# baby_monitor_v1.net
KiCad netlist of a schematic drawn in EAGLE
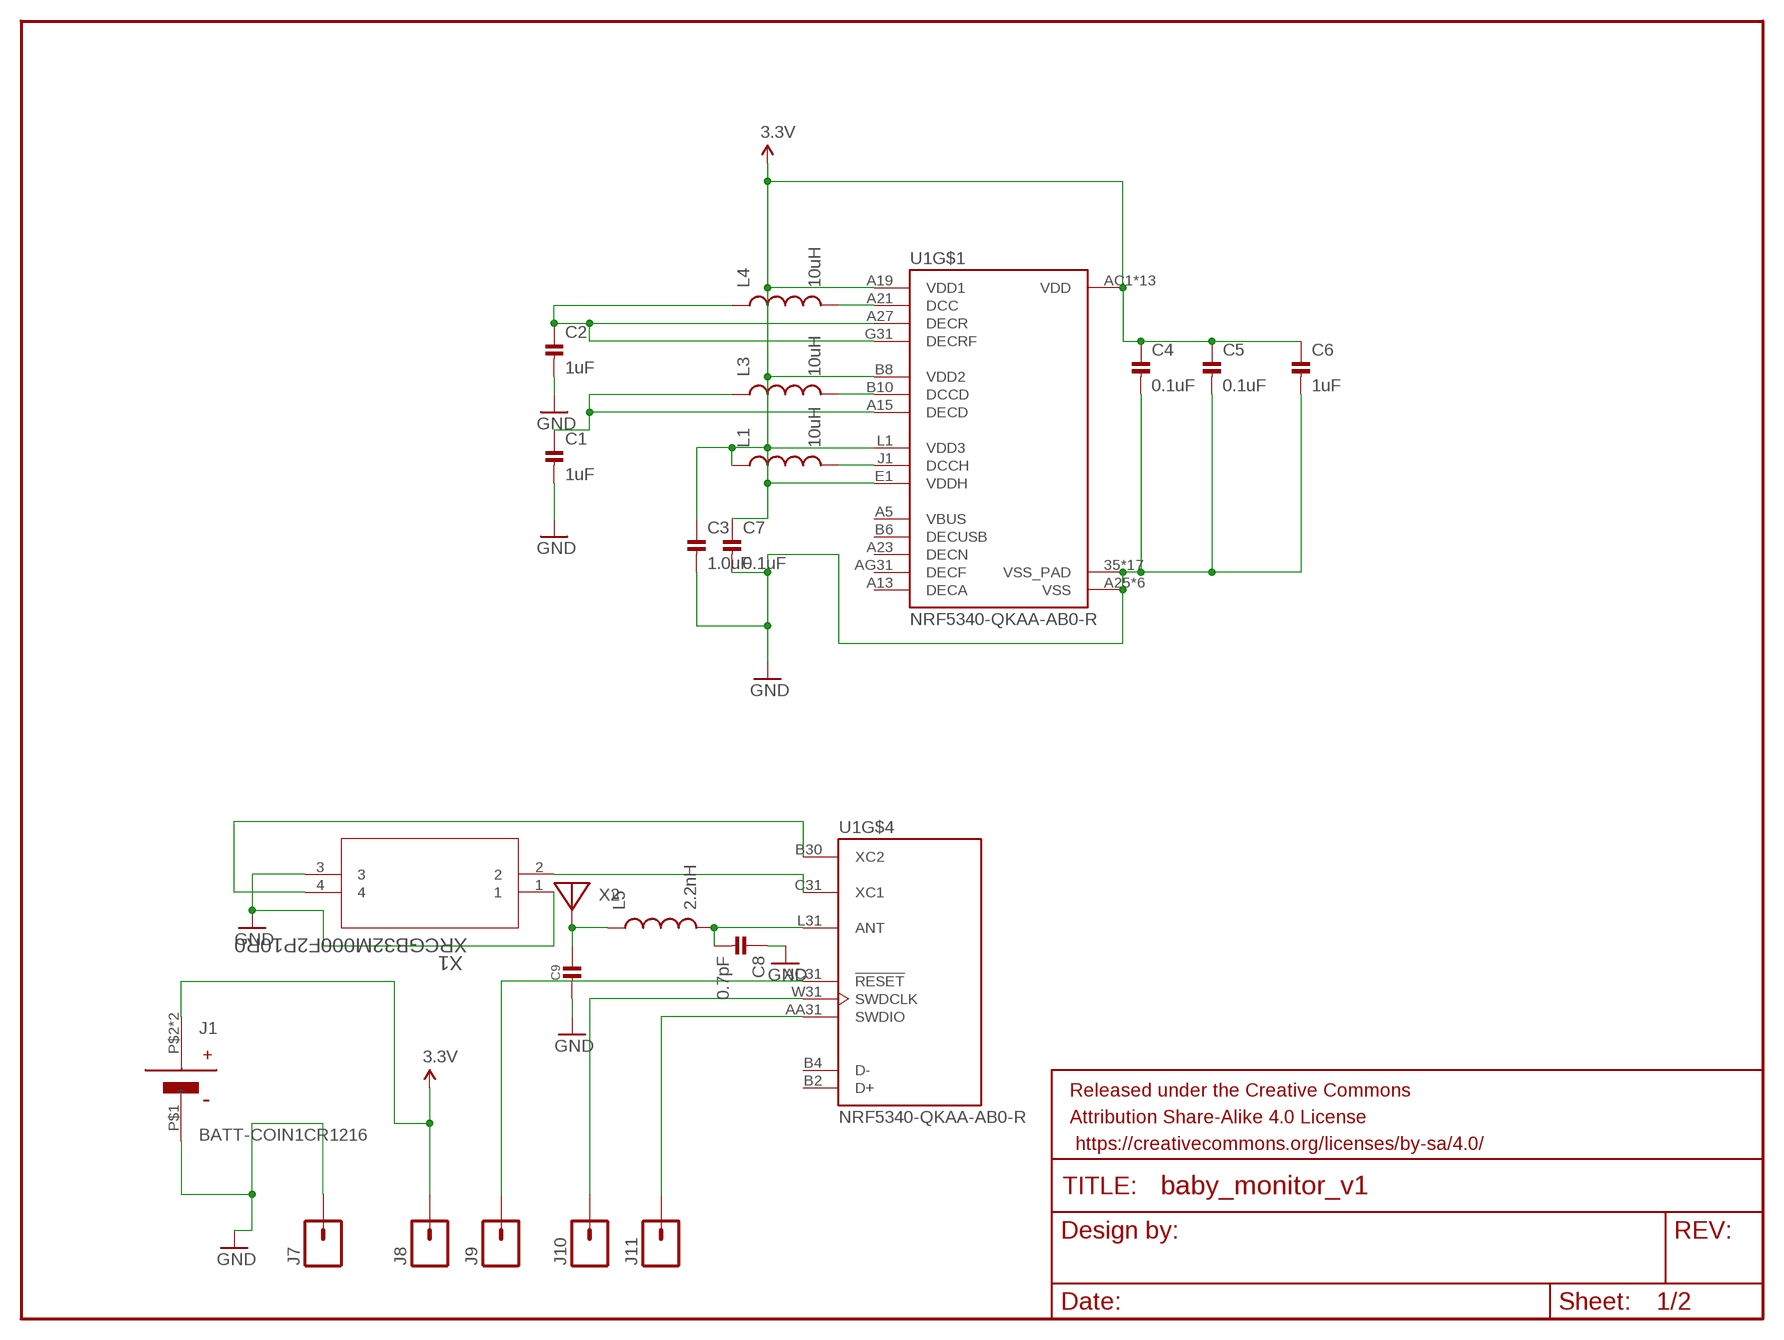
[diagram p0: schematic, sheet 1]
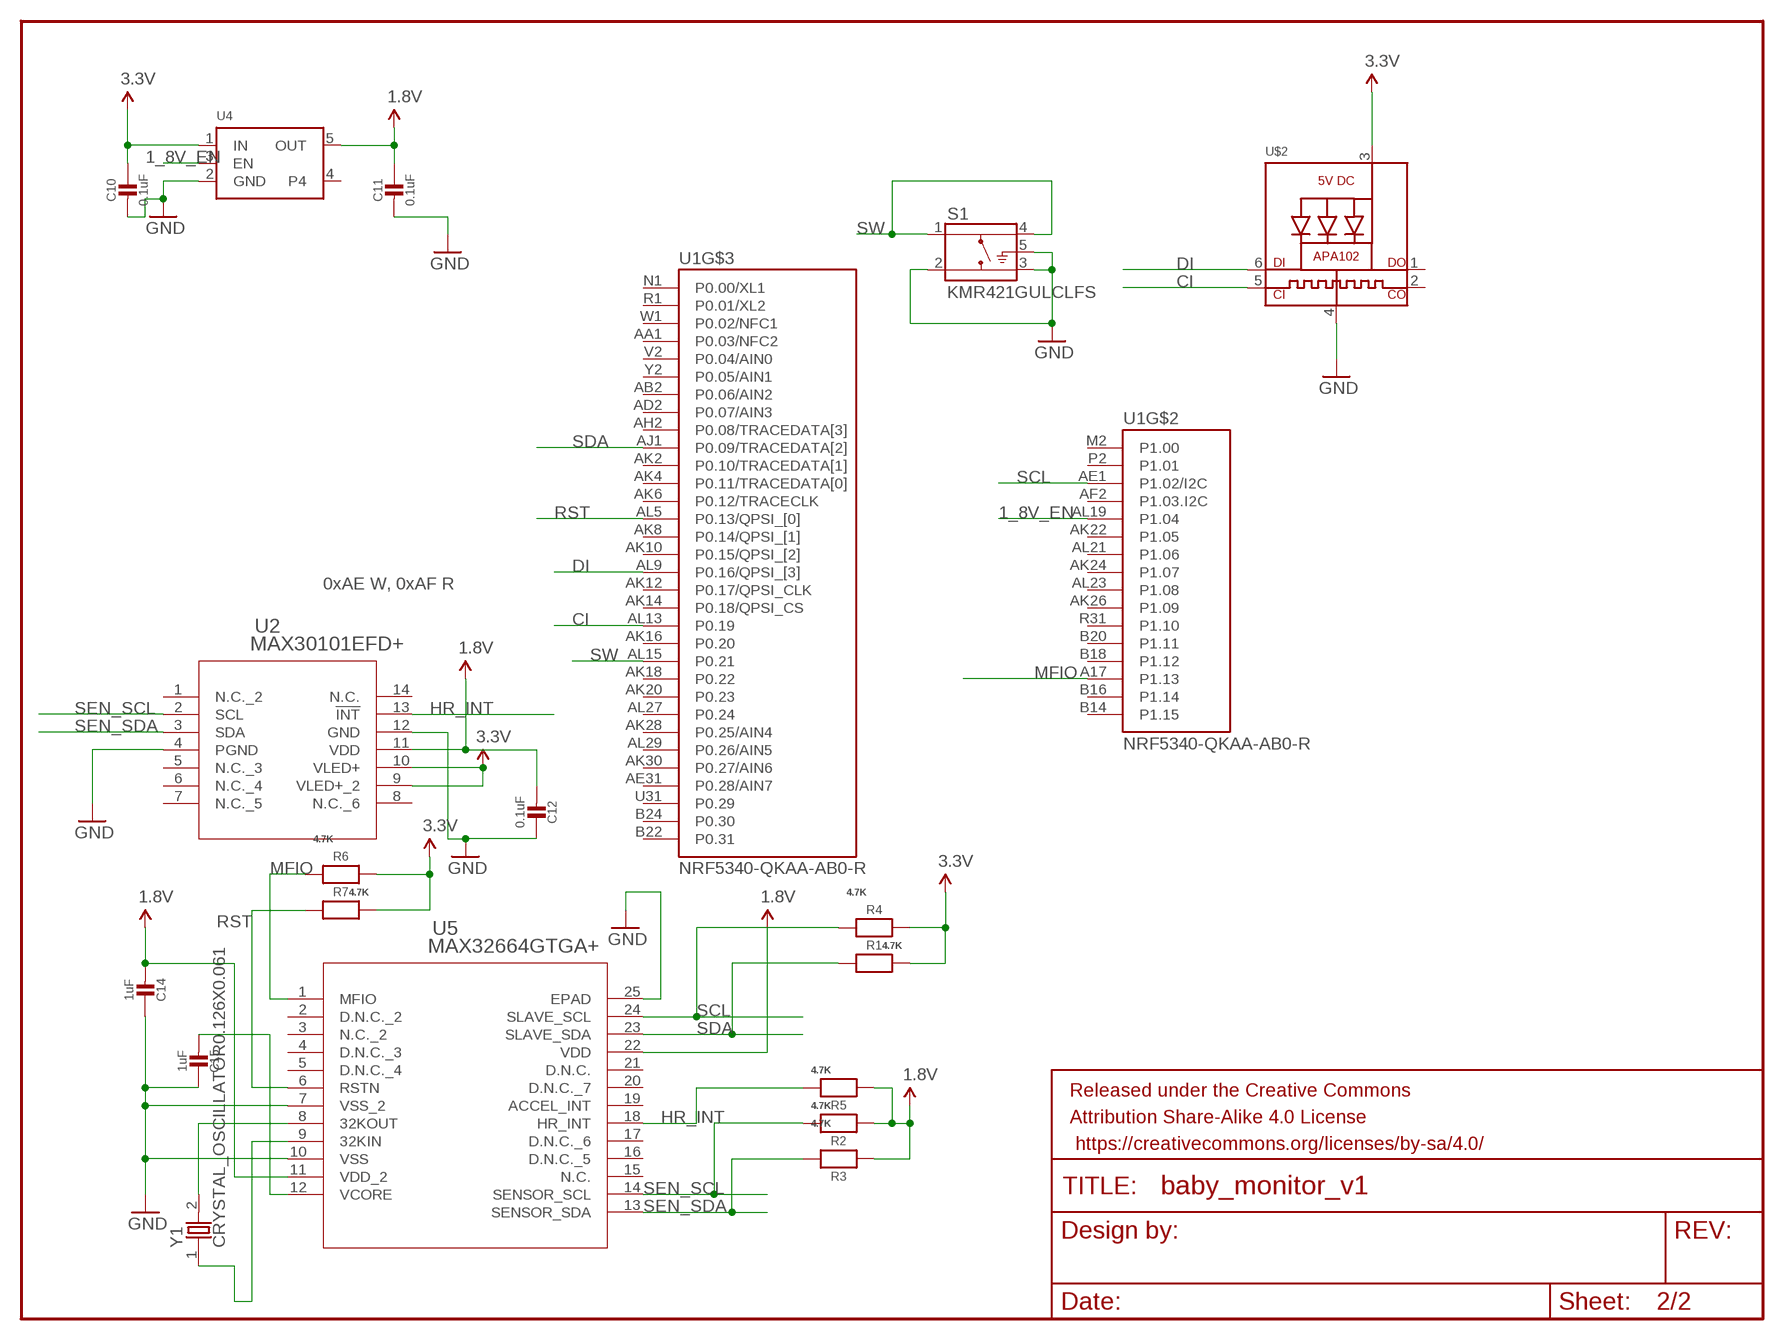
[diagram p1: schematic, sheet 2]

(export (version "E")
  (design (tool "Eeschema 10.0.6"))
  (components
    (comp (ref "C1")
      (value "1uF")
      (footprint "eagle-import:MICROBUILDER__0402MP")
      (libsource (lib "eagle-import") (part "MICROBUILDER_CAP_CERAMIC_0402MP"))
    )
    (comp (ref "C2")
      (value "1uF")
      (footprint "eagle-import:MICROBUILDER__0402MP")
      (libsource (lib "eagle-import") (part "MICROBUILDER_CAP_CERAMIC_0402MP"))
    )
    (comp (ref "C3")
      (value "1.0uF")
      (footprint "eagle-import:MICROBUILDER__0402MP")
      (libsource (lib "eagle-import") (part "MICROBUILDER_CAP_CERAMIC_0402MP"))
    )
    (comp (ref "C4")
      (value "0.1uF")
      (footprint "eagle-import:MICROBUILDER__0402MP")
      (libsource (lib "eagle-import") (part "MICROBUILDER_CAP_CERAMIC_0402MP"))
    )
    (comp (ref "C5")
      (value "0.1uF")
      (footprint "eagle-import:MICROBUILDER__0402MP")
      (libsource (lib "eagle-import") (part "MICROBUILDER_CAP_CERAMIC_0402MP"))
    )
    (comp (ref "C6")
      (value "1uF")
      (footprint "eagle-import:MICROBUILDER__0402MP")
      (libsource (lib "eagle-import") (part "MICROBUILDER_CAP_CERAMIC_0402MP"))
    )
    (comp (ref "C7")
      (value "0.1uF")
      (footprint "eagle-import:MICROBUILDER__0402MP")
      (libsource (lib "eagle-import") (part "MICROBUILDER_CAP_CERAMIC_0402MP"))
    )
    (comp (ref "C8")
      (value "0.7pF")
      (footprint "eagle-import:MICROBUILDER__0402MP")
      (libsource (lib "eagle-import") (part "MICROBUILDER_CAP_CERAMIC_0402MP"))
    )
    (comp (ref "C9")
      (value "MICROBUILDER_CAP_CERAMIC_0402MP")
      (footprint "eagle-import:MICROBUILDER__0402MP")
      (libsource (lib "eagle-import") (part "graftel-internal-ic_MICROBUILDER_CAP_CERAMIC_0402MP"))
    )
    (comp (ref "FRAME1")
      (value "FRAME-LETTERNO_PACKAGE")
      (footprint "eagle-import:DUMMY")
      (fields (field (name "DESIGNER") "Nobody"))
      (libsource (lib "eagle-import") (part "FRAME-LETTERNO_PACKAGE"))
    )
    (comp (ref "J1")
      (value "BATT-COIN1CR1216")
      (footprint "eagle-import:BC-2017-TR")
      (libsource (lib "eagle-import") (part "BATT-COIN1CR1216"))
    )
    (comp (ref "J7")
      (value "M01TINY")
      (footprint "eagle-import:1X01_TINY")
      (libsource (lib "eagle-import") (part "M01TINY"))
    )
    (comp (ref "J8")
      (value "M01TINY")
      (footprint "eagle-import:1X01_TINY")
      (libsource (lib "eagle-import") (part "M01TINY"))
    )
    (comp (ref "J9")
      (value "M01TINY")
      (footprint "eagle-import:1X01_TINY")
      (libsource (lib "eagle-import") (part "M01TINY"))
    )
    (comp (ref "J10")
      (value "M01TINY")
      (footprint "eagle-import:1X01_TINY")
      (libsource (lib "eagle-import") (part "M01TINY"))
    )
    (comp (ref "J11")
      (value "M01TINY")
      (footprint "eagle-import:1X01_TINY")
      (libsource (lib "eagle-import") (part "M01TINY"))
    )
    (comp (ref "L1")
      (value "10uH")
      (footprint "eagle-import:NORDIC_MISC_RESC0603_N")
      (libsource (lib "eagle-import") (part "NORDIC_MISC_INDUCTOR_0603_N"))
    )
    (comp (ref "L3")
      (value "10uH")
      (footprint "eagle-import:NORDIC_MISC_RESC0603_N")
      (libsource (lib "eagle-import") (part "NORDIC_MISC_INDUCTOR_0603_N"))
    )
    (comp (ref "L4")
      (value "10uH")
      (footprint "eagle-import:NORDIC_MISC_RESC0603_N")
      (libsource (lib "eagle-import") (part "NORDIC_MISC_INDUCTOR_0603_N"))
    )
    (comp (ref "L5")
      (value "2.2nH")
      (footprint "eagle-import:NORDIC_MISC_RESC0402_N")
      (libsource (lib "eagle-import") (part "NORDIC_MISC_INDUCTOR_0402_N"))
    )
    (comp (ref "U1")
      (value "NRF5340-QKAA-AB0-R")
      (footprint "eagle-import:XCVR_NRF5340-QKAA-AB0-R")
      (fields (field (name "MF") "Nordic Semiconductor") (field (name "MP") "nRF5340-QKAA-AB0-R"))
      (libsource (lib "eagle-import") (part "NRF5340-QKAA-AB0-R"))
    )
    (comp (ref "X1")
      (value "XRCGB32M000F2P10R0")
      (footprint "eagle-import:XTAL_SON4_1P6X2P0_MUR")
      (fields (field (name "DIGIKEY_PART") "490-14308-1-ND"))
      (libsource (lib "eagle-import") (part "XRCGB32M000F2P10R0"))
    )
    (comp (ref "X2")
      (value "ADAFRUIT_WIRELESS_ANTENNA_JOHANSON_2450AT18B100")
      (footprint "eagle-import:ADAFRUIT_WIRELESS_ANT_2450AT18B100")
      (fields (field (name "DIGIKEY_PART") "712-1006-1-ND"))
      (libsource (lib "eagle-import") (part "ADAFRUIT_WIRELESS_ANTENNA_JOHANSON_2450AT18B100"))
    )
    (comp (ref "C10")
      (value "0.1uF")
      (footprint "eagle-import:MICROBUILDER__0402MP")
      (libsource (lib "eagle-import") (part "MICROBUILDER_CAP_CERAMIC_0402MP"))
    )
    (comp (ref "C11")
      (value "0.1uF")
      (footprint "eagle-import:MICROBUILDER__0402MP")
      (libsource (lib "eagle-import") (part "MICROBUILDER_CAP_CERAMIC_0402MP"))
    )
    (comp (ref "C12")
      (value "0.1uF")
      (footprint "eagle-import:MICROBUILDER__0402MP")
      (libsource (lib "eagle-import") (part "MICROBUILDER_CAP_CERAMIC_0402MP"))
    )
    (comp (ref "C14")
      (value "1uF")
      (footprint "eagle-import:MICROBUILDER__0402MP")
      (libsource (lib "eagle-import") (part "MICROBUILDER_CAP_CERAMIC_0402MP"))
    )
    (comp (ref "C15")
      (value "1uF")
      (footprint "eagle-import:MICROBUILDER__0402MP")
      (libsource (lib "eagle-import") (part "MICROBUILDER_CAP_CERAMIC_0402MP"))
    )
    (comp (ref "FRAME2")
      (value "FRAME-LETTERNO_PACKAGE")
      (footprint "eagle-import:DUMMY")
      (fields (field (name "DESIGNER") "Nobody"))
      (libsource (lib "eagle-import") (part "FRAME-LETTERNO_PACKAGE"))
    )
    (comp (ref "R1")
      (value "4.7K")
      (footprint "eagle-import:MICROBUILDER__0402MP")
      (libsource (lib "eagle-import") (part "MICROBUILDER_RESISTOR_0402MP"))
    )
    (comp (ref "R2")
      (value "4.7K")
      (footprint "eagle-import:MICROBUILDER__0402MP")
      (libsource (lib "eagle-import") (part "MICROBUILDER_RESISTOR_0402MP"))
    )
    (comp (ref "R3")
      (value "4.7K")
      (footprint "eagle-import:MICROBUILDER__0402MP")
      (libsource (lib "eagle-import") (part "MICROBUILDER_RESISTOR_0402MP"))
    )
    (comp (ref "R4")
      (value "4.7K")
      (footprint "eagle-import:MICROBUILDER__0402MP")
      (libsource (lib "eagle-import") (part "MICROBUILDER_RESISTOR_0402MP"))
    )
    (comp (ref "R5")
      (value "4.7K")
      (footprint "eagle-import:MICROBUILDER__0402MP")
      (libsource (lib "eagle-import") (part "MICROBUILDER_RESISTOR_0402MP"))
    )
    (comp (ref "R6")
      (value "4.7K")
      (footprint "eagle-import:MICROBUILDER__0402MP")
      (libsource (lib "eagle-import") (part "MICROBUILDER_RESISTOR_0402MP"))
    )
    (comp (ref "R7")
      (value "4.7K")
      (footprint "eagle-import:MICROBUILDER__0402MP")
      (libsource (lib "eagle-import") (part "MICROBUILDER_RESISTOR_0402MP"))
    )
    (comp (ref "S1")
      (value "KMR421GULCLFS")
      (footprint "eagle-import:SW_KMR421GULCLFS")
      (fields (field (name "DIGI-KEY_PART_NUMBER") "CKN12152CT-ND") (field (name "MF") "C&K"))
      (libsource (lib "eagle-import") (part "KMR421GULCLFS"))
    )
    (comp (ref "U$2")
      (value "MICROBUILDER_APA1022020")
      (footprint "eagle-import:MICROBUILDER_APA102_2020")
      (libsource (lib "eagle-import") (part "MICROBUILDER_APA1022020"))
    )
    (comp (ref "U2")
      (value "MAX30101EFD+")
      (footprint "eagle-import:21-0880B_MXM")
      (libsource (lib "eagle-import") (part "MAX30101EFD+"))
    )
    (comp (ref "U4")
      (value "MICROBUILDER_VREG_SOT23-5")
      (footprint "eagle-import:MICROBUILDER_SOT23-5")
      (libsource (lib "eagle-import") (part "MICROBUILDER_VREG_SOT23-5"))
    )
    (comp (ref "U5")
      (value "MAX32664GTGA+")
      (footprint "eagle-import:21-100264_90-100089_MXM")
      (fields (field (name "COPYRIGHT") "Copyright (C) 2018 Accelerated Designs. All rights reserved"))
      (libsource (lib "eagle-import") (part "MAX32664GTGA+"))
    )
    (comp (ref "Y1")
      (value "CRYSTAL_OSCILLATOR0.126X0.061")
      (footprint "eagle-import:QUARTZ")
      (fields (field (name "PARTNO") "SER4072CT-ND "))
      (libsource (lib "eagle-import") (part "CRYSTAL_OSCILLATOR0.126X0.061"))
    )
  )
  (nets
    (net (code "1") (name "1.8V") (class "Default")
      (node (ref "C11") (pin "1") (pinfunction "1_1") (pintype "passive"))
      (node (ref "C12") (pin "2") (pinfunction "2_2") (pintype "passive"))
      (node (ref "C14") (pin "2") (pinfunction "2_2") (pintype "passive"))
      (node (ref "R2") (pin "1") (pinfunction "1_1") (pintype "passive"))
      (node (ref "R3") (pin "1") (pinfunction "1_1") (pintype "passive"))
      (node (ref "R5") (pin "1") (pinfunction "1_1") (pintype "passive"))
      (node (ref "U2") (pin "11") (pinfunction "VDD_11") (pintype "power_in"))
      (node (ref "U4") (pin "5") (pinfunction "OUT_5") (pintype "power_in"))
      (node (ref "U5") (pin "11") (pinfunction "VDD_2_11") (pintype "power_in"))
      (node (ref "U5") (pin "22") (pinfunction "VDD_22") (pintype "power_in"))
    )
    (net (code "2") (name "1_8V_EN") (class "Default")
      (node (ref "U1") (pin "AL19") (pinfunction "P1.04_AL19") (pintype "bidirectional"))
      (node (ref "U4") (pin "3") (pinfunction "EN_3") (pintype "input"))
    )
    (net (code "3") (name "3.3V") (class "Default")
      (node (ref "C10") (pin "1") (pinfunction "1_1") (pintype "passive"))
      (node (ref "C3") (pin "1") (pinfunction "1_1") (pintype "passive"))
      (node (ref "C4") (pin "1") (pinfunction "1_1") (pintype "passive"))
      (node (ref "C5") (pin "1") (pinfunction "1_1") (pintype "passive"))
      (node (ref "C6") (pin "1") (pinfunction "1_1") (pintype "passive"))
      (node (ref "C7") (pin "1") (pinfunction "1_1") (pintype "passive"))
      (node (ref "J1") (pin "P$2") (pinfunction "+_P$2") (pintype "bidirectional"))
      (node (ref "J1") (pin "P$3") (pinfunction "+_P$3") (pintype "bidirectional"))
      (node (ref "J8") (pin "P$1") (pinfunction "1_P$1") (pintype "passive"))
      (node (ref "L1") (pin "1") (pinfunction "1_1") (pintype "passive"))
      (node (ref "R1") (pin "2") (pinfunction "2_2") (pintype "passive"))
      (node (ref "R4") (pin "2") (pinfunction "2_2") (pintype "passive"))
      (node (ref "R6") (pin "2") (pinfunction "2_2") (pintype "passive"))
      (node (ref "R7") (pin "2") (pinfunction "2_2") (pintype "passive"))
      (node (ref "U$2") (pin "3") (pinfunction "VDD_3") (pintype "power_in"))
      (node (ref "U1") (pin "A19") (pinfunction "VDD1_A19") (pintype "power_in"))
      (node (ref "U1") (pin "AC1") (pinfunction "VDD_AC1") (pintype "power_in"))
      (node (ref "U1") (pin "AG1") (pinfunction "VDD_AG1") (pintype "power_in"))
      (node (ref "U1") (pin "AJ31") (pinfunction "VDD_AJ31") (pintype "power_in"))
      (node (ref "U1") (pin "AL11") (pinfunction "VDD_AL11") (pintype "power_in"))
      (node (ref "U1") (pin "AL17") (pinfunction "VDD_AL17") (pintype "power_in"))
      (node (ref "U1") (pin "AL25") (pinfunction "VDD_AL25") (pintype "power_in"))
      (node (ref "U1") (pin "AL3") (pinfunction "VDD_AL3") (pintype "power_in"))
      (node (ref "U1") (pin "AL7") (pinfunction "VDD_AL7") (pintype "power_in"))
      (node (ref "U1") (pin "B28") (pinfunction "VDD_B28") (pintype "power_in"))
      (node (ref "U1") (pin "B8") (pinfunction "VDD2_B8") (pintype "power_in"))
      (node (ref "U1") (pin "C1") (pinfunction "VDD_C1") (pintype "power_in"))
      (node (ref "U1") (pin "E1") (pinfunction "VDDH_E1") (pintype "power_in"))
      (node (ref "U1") (pin "E31") (pinfunction "VDD_E31") (pintype "power_in"))
      (node (ref "U1") (pin "L1") (pinfunction "VDD3_L1") (pintype "power_in"))
      (node (ref "U1") (pin "N31") (pinfunction "VDD_N31") (pintype "power_in"))
      (node (ref "U1") (pin "U1") (pinfunction "VDD_U1") (pintype "power_in"))
      (node (ref "U2") (pin "10") (pinfunction "VLED+_10") (pintype "passive"))
      (node (ref "U2") (pin "9") (pinfunction "VLED+_2_9") (pintype "passive"))
      (node (ref "U4") (pin "1") (pinfunction "IN_1") (pintype "power_in"))
    )
    (net (code "4") (name "CI") (class "Default")
      (node (ref "U$2") (pin "5") (pinfunction "CKI_5") (pintype "input"))
      (node (ref "U1") (pin "AL13") (pinfunction "P0.19_AL13") (pintype "bidirectional"))
    )
    (net (code "5") (name "DECA") (class "Default")
      (node (ref "U1") (pin "A13") (pinfunction "DECA_A13") (pintype "power_in"))
    )
    (net (code "6") (name "DECF") (class "Default")
      (node (ref "U1") (pin "AG31") (pinfunction "DECF_AG31") (pintype "power_in"))
    )
    (net (code "7") (name "DECN") (class "Default")
      (node (ref "U1") (pin "A23") (pinfunction "DECN_A23") (pintype "power_in"))
    )
    (net (code "8") (name "DECUSB") (class "Default")
      (node (ref "U1") (pin "B6") (pinfunction "DECUSB_B6") (pintype "power_in"))
    )
    (net (code "9") (name "DI") (class "Default")
      (node (ref "U$2") (pin "6") (pinfunction "DI_6") (pintype "input"))
      (node (ref "U1") (pin "AL9") (pinfunction "P0.16/QPSI_[3]_AL9") (pintype "bidirectional"))
    )
    (net (code "10") (name "GND") (class "Default")
      (node (ref "C1") (pin "2") (pinfunction "2_2") (pintype "passive"))
      (node (ref "C10") (pin "2") (pinfunction "2_2") (pintype "passive"))
      (node (ref "C11") (pin "2") (pinfunction "2_2") (pintype "passive"))
      (node (ref "C12") (pin "1") (pinfunction "1_1") (pintype "passive"))
      (node (ref "C14") (pin "1") (pinfunction "1_1") (pintype "passive"))
      (node (ref "C15") (pin "1") (pinfunction "1_1") (pintype "passive"))
      (node (ref "C2") (pin "2") (pinfunction "2_2") (pintype "passive"))
      (node (ref "C3") (pin "2") (pinfunction "2_2") (pintype "passive"))
      (node (ref "C4") (pin "2") (pinfunction "2_2") (pintype "passive"))
      (node (ref "C5") (pin "2") (pinfunction "2_2") (pintype "passive"))
      (node (ref "C6") (pin "2") (pinfunction "2_2") (pintype "passive"))
      (node (ref "C7") (pin "2") (pinfunction "2_2") (pintype "passive"))
      (node (ref "C8") (pin "1") (pinfunction "1_1") (pintype "passive"))
      (node (ref "C9") (pin "2") (pinfunction "2_2") (pintype "passive"))
      (node (ref "J1") (pin "P$1") (pinfunction "-_P$1") (pintype "bidirectional"))
      (node (ref "J7") (pin "P$1") (pinfunction "1_P$1") (pintype "passive"))
      (node (ref "S1") (pin "2") (pinfunction "2_2") (pintype "passive"))
      (node (ref "S1") (pin "3") (pinfunction "3_3") (pintype "passive"))
      (node (ref "S1") (pin "5") (pinfunction "G_5") (pintype "power_in"))
      (node (ref "U$2") (pin "4") (pinfunction "GND_4") (pintype "power_in"))
      (node (ref "U1") (pin "104") (pinfunction "VSS_PAD_104") (pintype "power_in"))
      (node (ref "U1") (pin "35") (pinfunction "VSS_PAD_35") (pintype "power_in"))
      (node (ref "U1") (pin "36") (pinfunction "VSS_PAD_36") (pintype "power_in"))
      (node (ref "U1") (pin "37") (pinfunction "VSS_PAD_37") (pintype "power_in"))
      (node (ref "U1") (pin "38") (pinfunction "VSS_PAD_38") (pintype "power_in"))
      (node (ref "U1") (pin "39") (pinfunction "VSS_PAD_39") (pintype "power_in"))
      (node (ref "U1") (pin "40") (pinfunction "VSS_PAD_40") (pintype "power_in"))
      (node (ref "U1") (pin "41") (pinfunction "VSS_PAD_41") (pintype "power_in"))
      (node (ref "U1") (pin "43") (pinfunction "VSS_PAD_43") (pintype "power_in"))
      (node (ref "U1") (pin "44") (pinfunction "VSS_PAD_44") (pintype "power_in"))
      (node (ref "U1") (pin "45") (pinfunction "VSS_PAD_45") (pintype "power_in"))
      (node (ref "U1") (pin "46") (pinfunction "VSS_PAD_46") (pintype "power_in"))
      (node (ref "U1") (pin "47") (pinfunction "VSS_PAD_47") (pintype "power_in"))
      (node (ref "U1") (pin "48") (pinfunction "VSS_PAD_48") (pintype "power_in"))
      (node (ref "U1") (pin "49") (pinfunction "VSS_PAD_49") (pintype "power_in"))
      (node (ref "U1") (pin "50") (pinfunction "VSS_PAD_50") (pintype "power_in"))
      (node (ref "U1") (pin "51") (pinfunction "VSS_PAD_51") (pintype "power_in"))
      (node (ref "U1") (pin "A25") (pinfunction "VSS_A25") (pintype "power_in"))
      (node (ref "U1") (pin "B12") (pinfunction "VSS_B12") (pintype "power_in"))
      (node (ref "U1") (pin "B26") (pinfunction "VSS_B26") (pintype "power_in"))
      (node (ref "U1") (pin "G1") (pinfunction "VSS_G1") (pintype "power_in"))
      (node (ref "U1") (pin "H2") (pinfunction "VSS_H2") (pintype "power_in"))
      (node (ref "U1") (pin "J31") (pinfunction "VSS_J31") (pintype "power_in"))
      (node (ref "U2") (pin "12") (pinfunction "GND_12") (pintype "passive"))
      (node (ref "U2") (pin "4") (pinfunction "PGND_4") (pintype "passive"))
      (node (ref "U4") (pin "2") (pinfunction "GND_2") (pintype "power_in"))
      (node (ref "U5") (pin "10") (pinfunction "VSS_10") (pintype "power_in"))
      (node (ref "U5") (pin "25") (pinfunction "EPAD_25") (pintype "power_in"))
      (node (ref "U5") (pin "7") (pinfunction "VSS_2_7") (pintype "power_in"))
      (node (ref "X1") (pin "1") (pinfunction "1_1") (pintype "passive"))
      (node (ref "X1") (pin "3") (pinfunction "3_3") (pintype "passive"))
    )
    (net (code "11") (name "HR_INT") (class "Default")
      (node (ref "R5") (pin "2") (pinfunction "2_2") (pintype "passive"))
      (node (ref "U2") (pin "13") (pinfunction "~{INT}_13") (pintype "passive"))
      (node (ref "U5") (pin "18") (pinfunction "HR_INT_18") (pintype "input"))
    )
    (net (code "12") (name "MFIO") (class "Default")
      (node (ref "R6") (pin "1") (pinfunction "1_1") (pintype "passive"))
      (node (ref "U1") (pin "A17") (pinfunction "P1.13_A17") (pintype "bidirectional"))
      (node (ref "U5") (pin "1") (pinfunction "MFIO_1") (pintype "bidirectional"))
    )
    (net (code "13") (name "Net-(J9-1)") (class "Default")
      (node (ref "J9") (pin "P$1") (pinfunction "1_P$1") (pintype "passive"))
      (node (ref "U1") (pin "AC31") (pinfunction "~{RESET}_AC31") (pintype "input"))
    )
    (net (code "14") (name "Net-(J10-1)") (class "Default")
      (node (ref "J10") (pin "P$1") (pinfunction "1_P$1") (pintype "passive"))
      (node (ref "U1") (pin "W31") (pinfunction "SWDCLK_W31") (pintype "input"))
    )
    (net (code "15") (name "Net-(J11-1)") (class "Default")
      (node (ref "J11") (pin "P$1") (pinfunction "1_P$1") (pintype "passive"))
      (node (ref "U1") (pin "AA31") (pinfunction "SWDIO_AA31") (pintype "bidirectional"))
    )
    (net (code "16") (name "Net-(U1A-DCC)") (class "Default")
      (node (ref "L4") (pin "2") (pinfunction "2_2") (pintype "passive"))
      (node (ref "U1") (pin "A21") (pinfunction "DCC_A21") (pintype "output"))
    )
    (net (code "17") (name "Net-(U1A-DCCD)") (class "Default")
      (node (ref "L3") (pin "2") (pinfunction "2_2") (pintype "passive"))
      (node (ref "U1") (pin "B10") (pinfunction "DCCD_B10") (pintype "power_in"))
    )
    (net (code "18") (name "Net-(U1A-DCCH)") (class "Default")
      (node (ref "L1") (pin "2") (pinfunction "2_2") (pintype "passive"))
      (node (ref "U1") (pin "J1") (pinfunction "DCCH_J1") (pintype "power_in"))
    )
    (net (code "19") (name "Net-(U1A-DECD)") (class "Default")
      (node (ref "C1") (pin "1") (pinfunction "1_1") (pintype "passive"))
      (node (ref "L3") (pin "1") (pinfunction "1_1") (pintype "passive"))
      (node (ref "U1") (pin "A15") (pinfunction "DECD_A15") (pintype "power_in"))
    )
    (net (code "20") (name "Net-(U1A-DECR)") (class "Default")
      (node (ref "C2") (pin "1") (pinfunction "1_1") (pintype "passive"))
      (node (ref "L4") (pin "1") (pinfunction "1_1") (pintype "passive"))
      (node (ref "U1") (pin "A27") (pinfunction "DECR_A27") (pintype "power_in"))
      (node (ref "U1") (pin "G31") (pinfunction "DECRF_G31") (pintype "power_in"))
    )
    (net (code "21") (name "Net-(U1D-ANT)") (class "Default")
      (node (ref "C8") (pin "2") (pinfunction "2_2") (pintype "passive"))
      (node (ref "L5") (pin "2") (pinfunction "2_2") (pintype "passive"))
      (node (ref "U1") (pin "L31") (pinfunction "ANT_L31") (pintype "bidirectional"))
    )
    (net (code "22") (name "Net-(U1D-XC1)") (class "Default")
      (node (ref "U1") (pin "C31") (pinfunction "XC1_C31") (pintype "input"))
      (node (ref "X1") (pin "2") (pinfunction "2_2") (pintype "passive"))
    )
    (net (code "23") (name "Net-(U1D-XC2)") (class "Default")
      (node (ref "U1") (pin "B30") (pinfunction "XC2_B30") (pintype "output"))
      (node (ref "X1") (pin "4") (pinfunction "4_4") (pintype "passive"))
    )
    (net (code "24") (name "Net-(U5-32KIN)") (class "Default")
      (node (ref "U5") (pin "9") (pinfunction "32KIN_9") (pintype "input"))
      (node (ref "Y1") (pin "1") (pinfunction "1_1") (pintype "passive"))
    )
    (net (code "25") (name "Net-(U5-32KOUT)") (class "Default")
      (node (ref "U5") (pin "8") (pinfunction "32KOUT_8") (pintype "output"))
      (node (ref "Y1") (pin "2") (pinfunction "2_2") (pintype "passive"))
    )
    (net (code "26") (name "Net-(U5-VCORE)") (class "Default")
      (node (ref "C15") (pin "2") (pinfunction "2_2") (pintype "passive"))
      (node (ref "U5") (pin "12") (pinfunction "VCORE_12") (pintype "power_in"))
    )
    (net (code "27") (name "Net-(X2-P$1)") (class "Default")
      (node (ref "C9") (pin "1") (pinfunction "1_1") (pintype "passive"))
      (node (ref "L5") (pin "1") (pinfunction "1_1") (pintype "passive"))
      (node (ref "X2") (pin "FP") (pinfunction "P$1_FP") (pintype "passive"))
    )
    (net (code "28") (name "RST") (class "Default")
      (node (ref "R7") (pin "1") (pinfunction "1_1") (pintype "passive"))
      (node (ref "U1") (pin "AL5") (pinfunction "P0.13/QPSI_[0]_AL5") (pintype "bidirectional"))
      (node (ref "U5") (pin "6") (pinfunction "RSTN_6") (pintype "input"))
    )
    (net (code "29") (name "SCL") (class "Default")
      (node (ref "R4") (pin "1") (pinfunction "1_1") (pintype "passive"))
      (node (ref "U1") (pin "AE1") (pinfunction "P1.02/I2C_AE1") (pintype "bidirectional"))
      (node (ref "U5") (pin "24") (pinfunction "SLAVE_SCL_24") (pintype "passive"))
    )
    (net (code "30") (name "SDA") (class "Default")
      (node (ref "R1") (pin "1") (pinfunction "1_1") (pintype "passive"))
      (node (ref "U1") (pin "AJ1") (pinfunction "P0.09/TRACEDATA[2]_AJ1") (pintype "bidirectional"))
      (node (ref "U5") (pin "23") (pinfunction "SLAVE_SDA_23") (pintype "passive"))
    )
    (net (code "31") (name "SEN_SCL") (class "Default")
      (node (ref "R2") (pin "2") (pinfunction "2_2") (pintype "passive"))
      (node (ref "U2") (pin "2") (pinfunction "SCL_2") (pintype "passive"))
      (node (ref "U5") (pin "14") (pinfunction "SENSOR_SCL_14") (pintype "passive"))
    )
    (net (code "32") (name "SEN_SDA") (class "Default")
      (node (ref "R3") (pin "2") (pinfunction "2_2") (pintype "passive"))
      (node (ref "U2") (pin "3") (pinfunction "SDA_3") (pintype "passive"))
      (node (ref "U5") (pin "13") (pinfunction "SENSOR_SDA_13") (pintype "passive"))
    )
    (net (code "33") (name "SW") (class "Default")
      (node (ref "S1") (pin "1") (pinfunction "1_1") (pintype "passive"))
      (node (ref "S1") (pin "4") (pinfunction "4_4") (pintype "passive"))
      (node (ref "U1") (pin "AL15") (pinfunction "P0.21_AL15") (pintype "bidirectional"))
    )
    (net (code "34") (name "VBUS") (class "Default")
      (node (ref "U1") (pin "A5") (pinfunction "VBUS_A5") (pintype "power_in"))
    )
    (net (code "35") (name "unconnected-(U$2-CKO-Pad2)") (class "Default")
      (node (ref "U$2") (pin "2") (pinfunction "CKO_2") (pintype "output"))
    )
    (net (code "36") (name "unconnected-(U$2-DO-Pad1)") (class "Default")
      (node (ref "U$2") (pin "1") (pinfunction "DO_1") (pintype "output"))
    )
    (net (code "37") (name "unconnected-(U1B-P1.00-PadM2)") (class "Default")
      (node (ref "U1") (pin "M2") (pinfunction "P1.00_M2") (pintype "bidirectional"))
    )
    (net (code "38") (name "unconnected-(U1B-P1.01-PadP2)") (class "Default")
      (node (ref "U1") (pin "P2") (pinfunction "P1.01_P2") (pintype "bidirectional"))
    )
    (net (code "39") (name "unconnected-(U1B-P1.03.I2C-PadAF2)") (class "Default")
      (node (ref "U1") (pin "AF2") (pinfunction "P1.03.I2C_AF2") (pintype "bidirectional"))
    )
    (net (code "40") (name "unconnected-(U1B-P1.05-PadAK22)") (class "Default")
      (node (ref "U1") (pin "AK22") (pinfunction "P1.05_AK22") (pintype "bidirectional"))
    )
    (net (code "41") (name "unconnected-(U1B-P1.06-PadAL21)") (class "Default")
      (node (ref "U1") (pin "AL21") (pinfunction "P1.06_AL21") (pintype "bidirectional"))
    )
    (net (code "42") (name "unconnected-(U1B-P1.07-PadAK24)") (class "Default")
      (node (ref "U1") (pin "AK24") (pinfunction "P1.07_AK24") (pintype "bidirectional"))
    )
    (net (code "43") (name "unconnected-(U1B-P1.08-PadAL23)") (class "Default")
      (node (ref "U1") (pin "AL23") (pinfunction "P1.08_AL23") (pintype "bidirectional"))
    )
    (net (code "44") (name "unconnected-(U1B-P1.09-PadAK26)") (class "Default")
      (node (ref "U1") (pin "AK26") (pinfunction "P1.09_AK26") (pintype "bidirectional"))
    )
    (net (code "45") (name "unconnected-(U1B-P1.10-PadR31)") (class "Default")
      (node (ref "U1") (pin "R31") (pinfunction "P1.10_R31") (pintype "bidirectional"))
    )
    (net (code "46") (name "unconnected-(U1B-P1.11-PadB20)") (class "Default")
      (node (ref "U1") (pin "B20") (pinfunction "P1.11_B20") (pintype "bidirectional"))
    )
    (net (code "47") (name "unconnected-(U1B-P1.12-PadB18)") (class "Default")
      (node (ref "U1") (pin "B18") (pinfunction "P1.12_B18") (pintype "bidirectional"))
    )
    (net (code "48") (name "unconnected-(U1B-P1.14-PadB16)") (class "Default")
      (node (ref "U1") (pin "B16") (pinfunction "P1.14_B16") (pintype "bidirectional"))
    )
    (net (code "49") (name "unconnected-(U1B-P1.15-PadB14)") (class "Default")
      (node (ref "U1") (pin "B14") (pinfunction "P1.15_B14") (pintype "bidirectional"))
    )
    (net (code "50") (name "unconnected-(U1C-P0.00{slash}XL1-PadN1)") (class "Default")
      (node (ref "U1") (pin "N1") (pinfunction "P0.00/XL1_N1") (pintype "bidirectional"))
    )
    (net (code "51") (name "unconnected-(U1C-P0.01{slash}XL2-PadR1)") (class "Default")
      (node (ref "U1") (pin "R1") (pinfunction "P0.01/XL2_R1") (pintype "bidirectional"))
    )
    (net (code "52") (name "unconnected-(U1C-P0.02{slash}NFC1-PadW1)") (class "Default")
      (node (ref "U1") (pin "W1") (pinfunction "P0.02/NFC1_W1") (pintype "bidirectional"))
    )
    (net (code "53") (name "unconnected-(U1C-P0.03{slash}NFC2-PadAA1)") (class "Default")
      (node (ref "U1") (pin "AA1") (pinfunction "P0.03/NFC2_AA1") (pintype "bidirectional"))
    )
    (net (code "54") (name "unconnected-(U1C-P0.04{slash}AIN0-PadV2)") (class "Default")
      (node (ref "U1") (pin "V2") (pinfunction "P0.04/AIN0_V2") (pintype "bidirectional"))
    )
    (net (code "55") (name "unconnected-(U1C-P0.05{slash}AIN1-PadY2)") (class "Default")
      (node (ref "U1") (pin "Y2") (pinfunction "P0.05/AIN1_Y2") (pintype "bidirectional"))
    )
    (net (code "56") (name "unconnected-(U1C-P0.06{slash}AIN2-PadAB2)") (class "Default")
      (node (ref "U1") (pin "AB2") (pinfunction "P0.06/AIN2_AB2") (pintype "bidirectional"))
    )
    (net (code "57") (name "unconnected-(U1C-P0.07{slash}AIN3-PadAD2)") (class "Default")
      (node (ref "U1") (pin "AD2") (pinfunction "P0.07/AIN3_AD2") (pintype "bidirectional"))
    )
    (net (code "58") (name "unconnected-(U1C-P0.08{slash}TRACEDATA[3]-PadAH2)") (class "Default")
      (node (ref "U1") (pin "AH2") (pinfunction "P0.08/TRACEDATA[3]_AH2") (pintype "bidirectional"))
    )
    (net (code "59") (name "unconnected-(U1C-P0.10{slash}TRACEDATA[1]-PadAK2)") (class "Default")
      (node (ref "U1") (pin "AK2") (pinfunction "P0.10/TRACEDATA[1]_AK2") (pintype "bidirectional"))
    )
    (net (code "60") (name "unconnected-(U1C-P0.11{slash}TRACEDATA[0]-PadAK4)") (class "Default")
      (node (ref "U1") (pin "AK4") (pinfunction "P0.11/TRACEDATA[0]_AK4") (pintype "bidirectional"))
    )
    (net (code "61") (name "unconnected-(U1C-P0.12{slash}TRACECLK-PadAK6)") (class "Default")
      (node (ref "U1") (pin "AK6") (pinfunction "P0.12/TRACECLK_AK6") (pintype "bidirectional"))
    )
    (net (code "62") (name "unconnected-(U1C-P0.14{slash}QPSI_[1]-PadAK8)") (class "Default")
      (node (ref "U1") (pin "AK8") (pinfunction "P0.14/QPSI_[1]_AK8") (pintype "bidirectional"))
    )
    (net (code "63") (name "unconnected-(U1C-P0.15{slash}QPSI_[2]-PadAK10)") (class "Default")
      (node (ref "U1") (pin "AK10") (pinfunction "P0.15/QPSI_[2]_AK10") (pintype "bidirectional"))
    )
    (net (code "64") (name "unconnected-(U1C-P0.17{slash}QPSI_CLK-PadAK12)") (class "Default")
      (node (ref "U1") (pin "AK12") (pinfunction "P0.17/QPSI_CLK_AK12") (pintype "bidirectional"))
    )
    (net (code "65") (name "unconnected-(U1C-P0.18{slash}QPSI_CS-PadAK14)") (class "Default")
      (node (ref "U1") (pin "AK14") (pinfunction "P0.18/QPSI_CS_AK14") (pintype "bidirectional"))
    )
    (net (code "66") (name "unconnected-(U1C-P0.20-PadAK16)") (class "Default")
      (node (ref "U1") (pin "AK16") (pinfunction "P0.20_AK16") (pintype "bidirectional"))
    )
    (net (code "67") (name "unconnected-(U1C-P0.22-PadAK18)") (class "Default")
      (node (ref "U1") (pin "AK18") (pinfunction "P0.22_AK18") (pintype "bidirectional"))
    )
    (net (code "68") (name "unconnected-(U1C-P0.23-PadAK20)") (class "Default")
      (node (ref "U1") (pin "AK20") (pinfunction "P0.23_AK20") (pintype "bidirectional"))
    )
    (net (code "69") (name "unconnected-(U1C-P0.24-PadAL27)") (class "Default")
      (node (ref "U1") (pin "AL27") (pinfunction "P0.24_AL27") (pintype "bidirectional"))
    )
    (net (code "70") (name "unconnected-(U1C-P0.25{slash}AIN4-PadAK28)") (class "Default")
      (node (ref "U1") (pin "AK28") (pinfunction "P0.25/AIN4_AK28") (pintype "bidirectional"))
    )
    (net (code "71") (name "unconnected-(U1C-P0.26{slash}AIN5-PadAL29)") (class "Default")
      (node (ref "U1") (pin "AL29") (pinfunction "P0.26/AIN5_AL29") (pintype "bidirectional"))
    )
    (net (code "72") (name "unconnected-(U1C-P0.27{slash}AIN6-PadAK30)") (class "Default")
      (node (ref "U1") (pin "AK30") (pinfunction "P0.27/AIN6_AK30") (pintype "bidirectional"))
    )
    (net (code "73") (name "unconnected-(U1C-P0.28{slash}AIN7-PadAE31)") (class "Default")
      (node (ref "U1") (pin "AE31") (pinfunction "P0.28/AIN7_AE31") (pintype "bidirectional"))
    )
    (net (code "74") (name "unconnected-(U1C-P0.29-PadU31)") (class "Default")
      (node (ref "U1") (pin "U31") (pinfunction "P0.29_U31") (pintype "bidirectional"))
    )
    (net (code "75") (name "unconnected-(U1C-P0.30-PadB24)") (class "Default")
      (node (ref "U1") (pin "B24") (pinfunction "P0.30_B24") (pintype "bidirectional"))
    )
    (net (code "76") (name "unconnected-(U1C-P0.31-PadB22)") (class "Default")
      (node (ref "U1") (pin "B22") (pinfunction "P0.31_B22") (pintype "bidirectional"))
    )
    (net (code "77") (name "unconnected-(U1D-D+-PadB2)") (class "Default")
      (node (ref "U1") (pin "B2") (pinfunction "D+_B2") (pintype "bidirectional"))
    )
    (net (code "78") (name "unconnected-(U1D-D--PadB4)") (class "Default")
      (node (ref "U1") (pin "B4") (pinfunction "D-_B4") (pintype "bidirectional"))
    )
    (net (code "79") (name "unconnected-(U2-N.C.-Pad14)") (class "Default")
      (node (ref "U2") (pin "14") (pinfunction "N.C._14") (pintype "no_connect"))
    )
    (net (code "80") (name "unconnected-(U2-N.C._2-Pad1)") (class "Default")
      (node (ref "U2") (pin "1") (pinfunction "N.C._2_1") (pintype "no_connect"))
    )
    (net (code "81") (name "unconnected-(U2-N.C._3-Pad5)") (class "Default")
      (node (ref "U2") (pin "5") (pinfunction "N.C._3_5") (pintype "no_connect"))
    )
    (net (code "82") (name "unconnected-(U2-N.C._4-Pad6)") (class "Default")
      (node (ref "U2") (pin "6") (pinfunction "N.C._4_6") (pintype "no_connect"))
    )
    (net (code "83") (name "unconnected-(U2-N.C._5-Pad7)") (class "Default")
      (node (ref "U2") (pin "7") (pinfunction "N.C._5_7") (pintype "no_connect"))
    )
    (net (code "84") (name "unconnected-(U2-N.C._6-Pad8)") (class "Default")
      (node (ref "U2") (pin "8") (pinfunction "N.C._6_8") (pintype "no_connect"))
    )
    (net (code "85") (name "unconnected-(U4-P4-Pad4)") (class "Default")
      (node (ref "U4") (pin "4") (pinfunction "P4_4") (pintype "bidirectional"))
    )
    (net (code "86") (name "unconnected-(U5-ACCEL_INT-Pad19)") (class "Default")
      (node (ref "U5") (pin "19") (pinfunction "ACCEL_INT_19") (pintype "input"))
    )
    (net (code "87") (name "unconnected-(U5-D.N.C.-Pad21)") (class "Default")
      (node (ref "U5") (pin "21") (pinfunction "D.N.C._21") (pintype "no_connect"))
    )
    (net (code "88") (name "unconnected-(U5-D.N.C._2-Pad2)") (class "Default")
      (node (ref "U5") (pin "2") (pinfunction "D.N.C._2_2") (pintype "no_connect"))
    )
    (net (code "89") (name "unconnected-(U5-D.N.C._3-Pad4)") (class "Default")
      (node (ref "U5") (pin "4") (pinfunction "D.N.C._3_4") (pintype "no_connect"))
    )
    (net (code "90") (name "unconnected-(U5-D.N.C._4-Pad5)") (class "Default")
      (node (ref "U5") (pin "5") (pinfunction "D.N.C._4_5") (pintype "no_connect"))
    )
    (net (code "91") (name "unconnected-(U5-D.N.C._5-Pad16)") (class "Default")
      (node (ref "U5") (pin "16") (pinfunction "D.N.C._5_16") (pintype "no_connect"))
    )
    (net (code "92") (name "unconnected-(U5-D.N.C._6-Pad17)") (class "Default")
      (node (ref "U5") (pin "17") (pinfunction "D.N.C._6_17") (pintype "no_connect"))
    )
    (net (code "93") (name "unconnected-(U5-D.N.C._7-Pad20)") (class "Default")
      (node (ref "U5") (pin "20") (pinfunction "D.N.C._7_20") (pintype "no_connect"))
    )
    (net (code "94") (name "unconnected-(U5-N.C.-Pad15)") (class "Default")
      (node (ref "U5") (pin "15") (pinfunction "N.C._15") (pintype "no_connect"))
    )
    (net (code "95") (name "unconnected-(U5-N.C._2-Pad3)") (class "Default")
      (node (ref "U5") (pin "3") (pinfunction "N.C._2_3") (pintype "no_connect"))
    )
  )
)
